# SparkFun_Qwiic_6DoF_BMI270.net
KiCad netlist of a schematic drawn in EAGLE
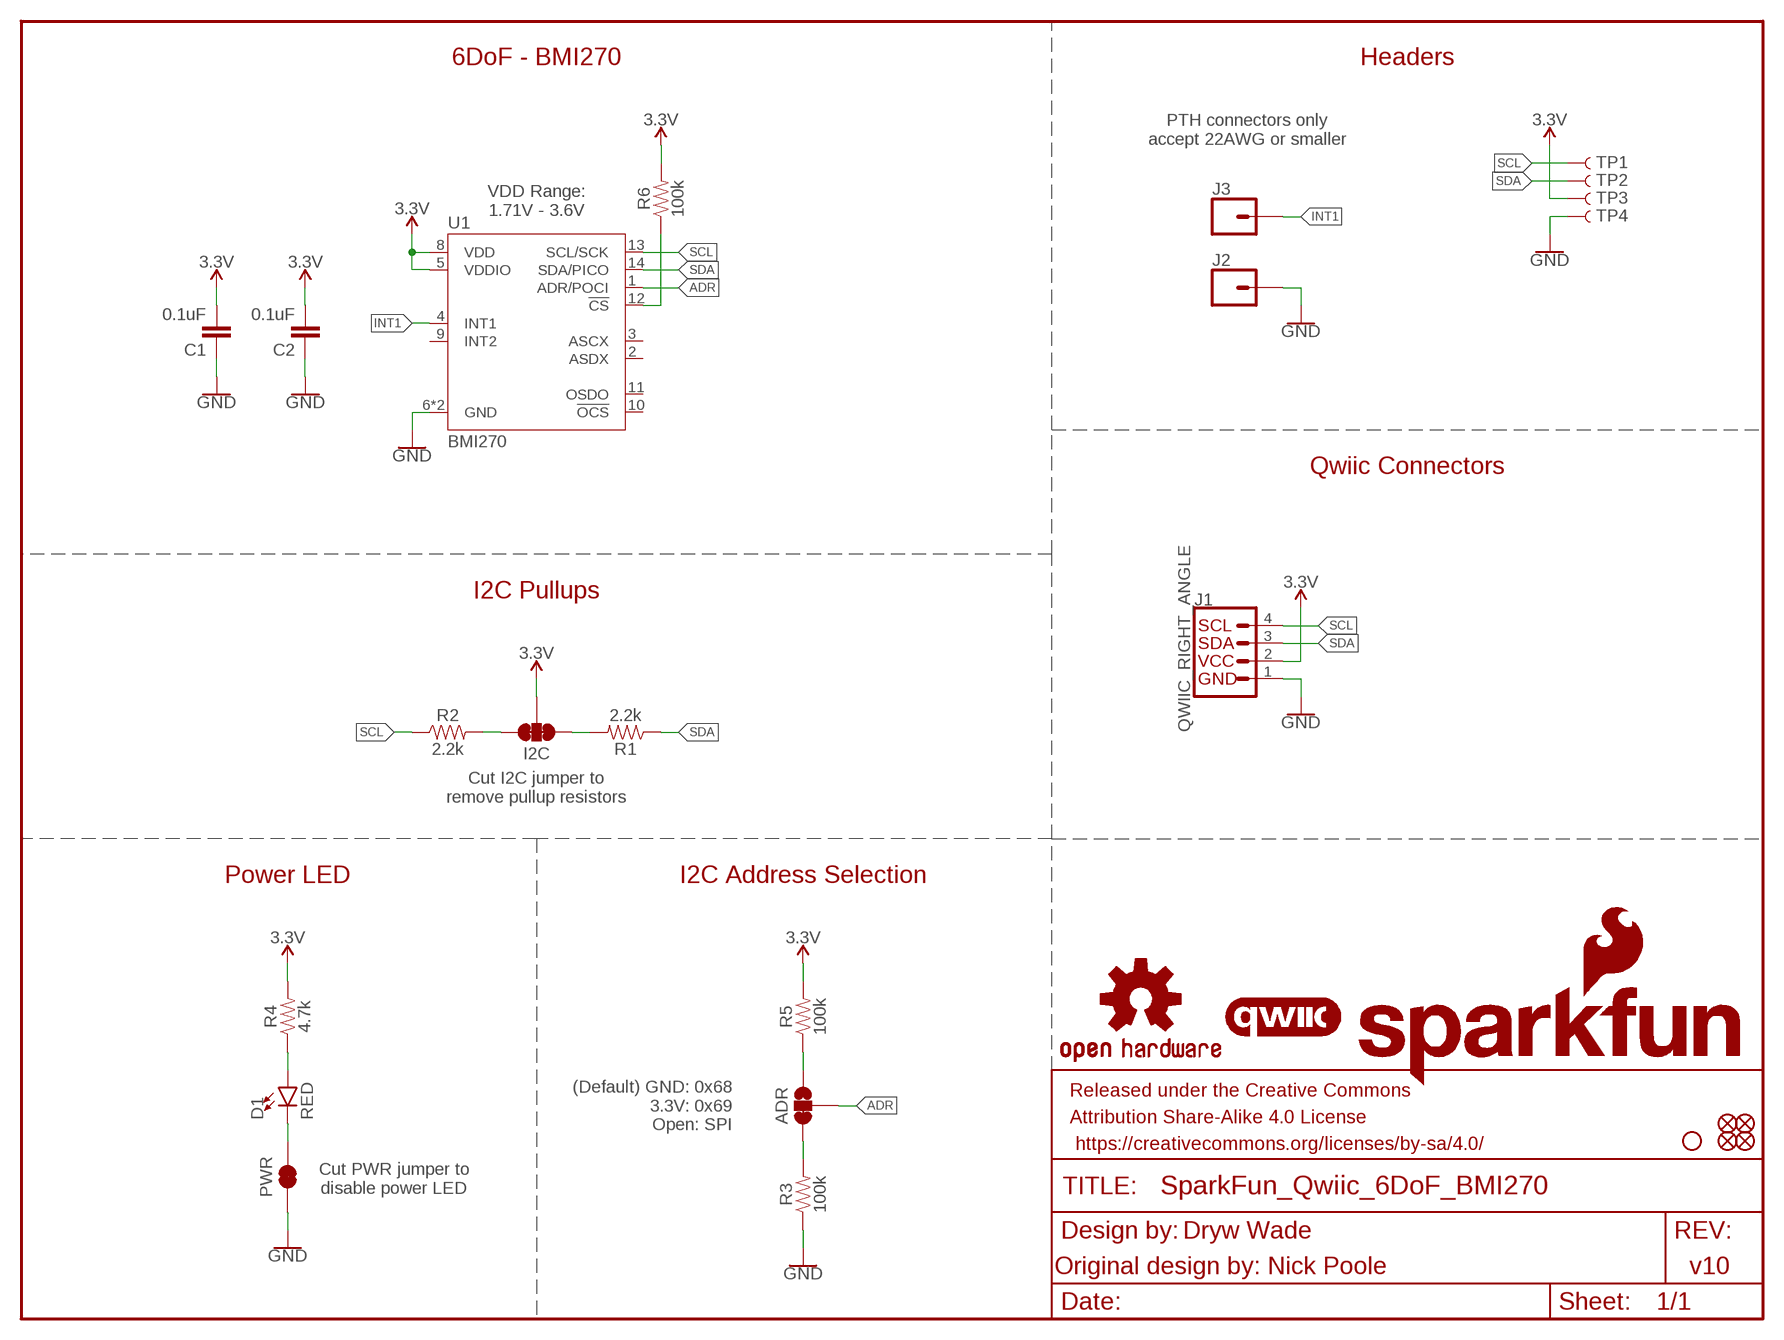
[diagram p0: schematic, sheet 1]

(export (version "E")
  (design (tool "Eeschema 10.0.6"))
  (components
    (comp (ref "ADR")
      (value "JUMPER-SMT_3_1-NC_TRACE_SILK")
      (footprint "eagle-import:SMT-JUMPER_3_1-NC_TRACE_SILK")
      (libsource (lib "eagle-import") (part "JUMPER-SMT_3_1-NC_TRACE_SILK"))
    )
    (comp (ref "C1")
      (value "0.1uF")
      (footprint "eagle-import:0402-TIGHT")
      (libsource (lib "eagle-import") (part "0.1UF-0402T-6.3V-10%-X7R"))
    )
    (comp (ref "C2")
      (value "0.1uF")
      (footprint "eagle-import:0402-TIGHT")
      (libsource (lib "eagle-import") (part "0.1UF-0402T-6.3V-10%-X7R"))
    )
    (comp (ref "D1")
      (value "RED")
      (footprint "eagle-import:LED-0402")
      (libsource (lib "eagle-import") (part "LED-RED_0402"))
    )
    (comp (ref "FD1")
      (value "FIDUCIALUFIDUCIAL")
      (footprint "eagle-import:FIDUCIAL-MICRO")
      (libsource (lib "eagle-import") (part "FIDUCIALUFIDUCIAL"))
    )
    (comp (ref "FD2")
      (value "FIDUCIALUFIDUCIAL")
      (footprint "eagle-import:FIDUCIAL-MICRO")
      (libsource (lib "eagle-import") (part "FIDUCIALUFIDUCIAL"))
    )
    (comp (ref "FD3")
      (value "FIDUCIALUFIDUCIAL")
      (footprint "eagle-import:FIDUCIAL-MICRO")
      (libsource (lib "eagle-import") (part "FIDUCIALUFIDUCIAL"))
    )
    (comp (ref "FD4")
      (value "FIDUCIALUFIDUCIAL")
      (footprint "eagle-import:FIDUCIAL-MICRO")
      (libsource (lib "eagle-import") (part "FIDUCIALUFIDUCIAL"))
    )
    (comp (ref "FRAME1")
      (value "FRAME-LETTER")
      (footprint "eagle-import:CREATIVE_COMMONS")
      (libsource (lib "eagle-import") (part "FRAME-LETTER"))
    )
    (comp (ref "H1")
      (value "STAND-OFF")
      (footprint "eagle-import:STAND-OFF")
      (libsource (lib "eagle-import") (part "STAND-OFF"))
    )
    (comp (ref "I2C")
      (value "JUMPER-SMT_3_2-NC_TRACE_SILK")
      (footprint "eagle-import:SMT-JUMPER_3_2-NC_TRACE_SILK")
      (libsource (lib "eagle-import") (part "JUMPER-SMT_3_2-NC_TRACE_SILK"))
    )
    (comp (ref "J1")
      (value "QWIIC_RIGHT_ANGLE")
      (footprint "eagle-import:JST04_1MM_RA")
      (libsource (lib "eagle-import") (part "QWIIC_CONNECTORJS-1MM"))
    )
    (comp (ref "J2")
      (value "CONN_01_1MM")
      (footprint "eagle-import:1X01_1MM_NO_SILK")
      (libsource (lib "eagle-import") (part "CONN_01_1MM"))
    )
    (comp (ref "J3")
      (value "CONN_01_1MM")
      (footprint "eagle-import:1X01_1MM_NO_SILK")
      (libsource (lib "eagle-import") (part "CONN_01_1MM"))
    )
    (comp (ref "LOGO1")
      (value "SFE_LOGO_NAME_FLAMEBLANK")
      (footprint "eagle-import:BLANK")
      (libsource (lib "eagle-import") (part "SFE_LOGO_NAME_FLAMEBLANK"))
    )
    (comp (ref "LOGO2")
      (value "QWIIC_LOGO_3MM")
      (footprint "eagle-import:QWIIC_3MM")
      (libsource (lib "eagle-import") (part "QWIIC_LOGO_3MM"))
    )
    (comp (ref "LOGO3")
      (value "OSHW-LOGOMINI")
      (footprint "eagle-import:OSHW-LOGO-MINI")
      (libsource (lib "eagle-import") (part "OSHW-LOGOMINI"))
    )
    (comp (ref "PWR")
      (value "JUMPER-SMT_2_NC_TRACE_SILK")
      (footprint "eagle-import:SMT-JUMPER_2_NC_TRACE_SILK")
      (libsource (lib "eagle-import") (part "JUMPER-SMT_2_NC_TRACE_SILK"))
    )
    (comp (ref "R1")
      (value "2.2k")
      (footprint "eagle-import:0402-TIGHT")
      (libsource (lib "eagle-import") (part "2.2KOHM-0402T-1/16W-1%"))
    )
    (comp (ref "R2")
      (value "2.2k")
      (footprint "eagle-import:0402-TIGHT")
      (libsource (lib "eagle-import") (part "2.2KOHM-0402T-1/16W-1%"))
    )
    (comp (ref "R3")
      (value "100k")
      (footprint "eagle-import:0402-TIGHT")
      (libsource (lib "eagle-import") (part "100KOHM-0402T-1/16W-1%"))
    )
    (comp (ref "R4")
      (value "4.7k")
      (footprint "eagle-import:0402-TIGHT")
      (libsource (lib "eagle-import") (part "4.7KOHM-0402T-1/16W-1%"))
    )
    (comp (ref "R5")
      (value "100k")
      (footprint "eagle-import:0402-TIGHT")
      (libsource (lib "eagle-import") (part "100KOHM-0402T-1/16W-1%"))
    )
    (comp (ref "R6")
      (value "100k")
      (footprint "eagle-import:0402-TIGHT")
      (libsource (lib "eagle-import") (part "100KOHM-0402T-1/16W-1%"))
    )
    (comp (ref "TP1")
      (value "TEST-POINT3")
      (footprint "eagle-import:PAD.03X.03")
      (libsource (lib "eagle-import") (part "TEST-POINT3"))
    )
    (comp (ref "TP2")
      (value "TEST-POINT3")
      (footprint "eagle-import:PAD.03X.03")
      (libsource (lib "eagle-import") (part "TEST-POINT3"))
    )
    (comp (ref "TP3")
      (value "TEST-POINT3")
      (footprint "eagle-import:PAD.03X.03")
      (libsource (lib "eagle-import") (part "TEST-POINT3"))
    )
    (comp (ref "TP4")
      (value "TEST-POINT3")
      (footprint "eagle-import:PAD.03X.03")
      (libsource (lib "eagle-import") (part "TEST-POINT3"))
    )
    (comp (ref "U1")
      (value "BMI270")
      (footprint "eagle-import:BMI270")
      (libsource (lib "eagle-import") (part "BMI270"))
    )
  )
  (nets
    (net (code "1") (name "3.3V") (class "Default")
      (node (ref "C1") (pin "2") (pinfunction "2_2") (pintype "passive"))
      (node (ref "C2") (pin "2") (pinfunction "2_2") (pintype "passive"))
      (node (ref "I2C") (pin "2") (pinfunction "2_2") (pintype "passive"))
      (node (ref "J1") (pin "2") (pinfunction "2_2") (pintype "power_in"))
      (node (ref "R4") (pin "2") (pinfunction "2_2") (pintype "passive"))
      (node (ref "R5") (pin "2") (pinfunction "2_2") (pintype "passive"))
      (node (ref "R6") (pin "2") (pinfunction "2_2") (pintype "passive"))
      (node (ref "TP3") (pin "1") (pinfunction "1_1") (pintype "bidirectional"))
      (node (ref "U1") (pin "5") (pinfunction "VDDIO_5") (pintype "bidirectional"))
      (node (ref "U1") (pin "8") (pinfunction "VDD_8") (pintype "bidirectional"))
    )
    (net (code "2") (name "ADR") (class "Default")
      (node (ref "ADR") (pin "2") (pinfunction "2_2") (pintype "passive"))
      (node (ref "U1") (pin "1") (pinfunction "ADR/POCI_1") (pintype "bidirectional"))
    )
    (net (code "3") (name "GND") (class "Default")
      (node (ref "C1") (pin "1") (pinfunction "1_1") (pintype "passive"))
      (node (ref "C2") (pin "1") (pinfunction "1_1") (pintype "passive"))
      (node (ref "J1") (pin "1") (pinfunction "1_1") (pintype "power_in"))
      (node (ref "J2") (pin "1") (pinfunction "1_1") (pintype "passive"))
      (node (ref "PWR") (pin "1") (pinfunction "1_1") (pintype "passive"))
      (node (ref "R3") (pin "1") (pinfunction "1_1") (pintype "passive"))
      (node (ref "TP4") (pin "1") (pinfunction "1_1") (pintype "bidirectional"))
      (node (ref "U1") (pin "6") (pinfunction "GND_6") (pintype "bidirectional"))
      (node (ref "U1") (pin "7") (pinfunction "GND_7") (pintype "bidirectional"))
    )
    (net (code "4") (name "INT1") (class "Default")
      (node (ref "J3") (pin "1") (pinfunction "1_1") (pintype "passive"))
      (node (ref "U1") (pin "4") (pinfunction "INT1_4") (pintype "bidirectional"))
    )
    (net (code "5") (name "Net-(ADR-Pad1)") (class "Default")
      (node (ref "ADR") (pin "1") (pinfunction "1_1") (pintype "passive"))
      (node (ref "R5") (pin "1") (pinfunction "1_1") (pintype "passive"))
    )
    (net (code "6") (name "Net-(ADR-Pad3)") (class "Default")
      (node (ref "ADR") (pin "3") (pinfunction "3_3") (pintype "passive"))
      (node (ref "R3") (pin "2") (pinfunction "2_2") (pintype "passive"))
    )
    (net (code "7") (name "Net-(D1-PadA)") (class "Default")
      (node (ref "D1") (pin "A") (pinfunction "A_A") (pintype "passive"))
      (node (ref "R4") (pin "1") (pinfunction "1_1") (pintype "passive"))
    )
    (net (code "8") (name "Net-(D1-PadC)") (class "Default")
      (node (ref "D1") (pin "C") (pinfunction "C_C") (pintype "passive"))
      (node (ref "PWR") (pin "2") (pinfunction "2_2") (pintype "passive"))
    )
    (net (code "9") (name "Net-(I2C-Pad1)") (class "Default")
      (node (ref "I2C") (pin "1") (pinfunction "1_1") (pintype "passive"))
      (node (ref "R1") (pin "2") (pinfunction "2_2") (pintype "passive"))
    )
    (net (code "10") (name "Net-(I2C-Pad3)") (class "Default")
      (node (ref "I2C") (pin "3") (pinfunction "3_3") (pintype "passive"))
      (node (ref "R2") (pin "2") (pinfunction "2_2") (pintype "passive"))
    )
    (net (code "11") (name "Net-(U1-~{CS})") (class "Default")
      (node (ref "R6") (pin "1") (pinfunction "1_1") (pintype "passive"))
      (node (ref "U1") (pin "12") (pinfunction "~{CS}_12") (pintype "bidirectional"))
    )
    (net (code "12") (name "SCL") (class "Default")
      (node (ref "J1") (pin "4") (pinfunction "4_4") (pintype "passive"))
      (node (ref "R2") (pin "1") (pinfunction "1_1") (pintype "passive"))
      (node (ref "TP1") (pin "1") (pinfunction "1_1") (pintype "bidirectional"))
      (node (ref "U1") (pin "13") (pinfunction "SCL/SCK_13") (pintype "bidirectional"))
    )
    (net (code "13") (name "SDA") (class "Default")
      (node (ref "J1") (pin "3") (pinfunction "3_3") (pintype "passive"))
      (node (ref "R1") (pin "1") (pinfunction "1_1") (pintype "passive"))
      (node (ref "TP2") (pin "1") (pinfunction "1_1") (pintype "bidirectional"))
      (node (ref "U1") (pin "14") (pinfunction "SDA/PICO_14") (pintype "bidirectional"))
    )
    (net (code "14") (name "unconnected-(U1-ASCX-Pad3)") (class "Default")
      (node (ref "U1") (pin "3") (pinfunction "ASCX_3") (pintype "bidirectional"))
    )
    (net (code "15") (name "unconnected-(U1-ASDX-Pad2)") (class "Default")
      (node (ref "U1") (pin "2") (pinfunction "ASDX_2") (pintype "bidirectional"))
    )
    (net (code "16") (name "unconnected-(U1-INT2-Pad9)") (class "Default")
      (node (ref "U1") (pin "9") (pinfunction "INT2_9") (pintype "bidirectional"))
    )
    (net (code "17") (name "unconnected-(U1-OSDO-Pad11)") (class "Default")
      (node (ref "U1") (pin "11") (pinfunction "OSDO_11") (pintype "bidirectional"))
    )
    (net (code "18") (name "unconnected-(U1-~{OCS}-Pad10)") (class "Default")
      (node (ref "U1") (pin "10") (pinfunction "~{OCS}_10") (pintype "bidirectional"))
    )
  )
)
